# HumidTempSleep_Feather_001sch.net
KiCad netlist of a schematic drawn in EAGLE
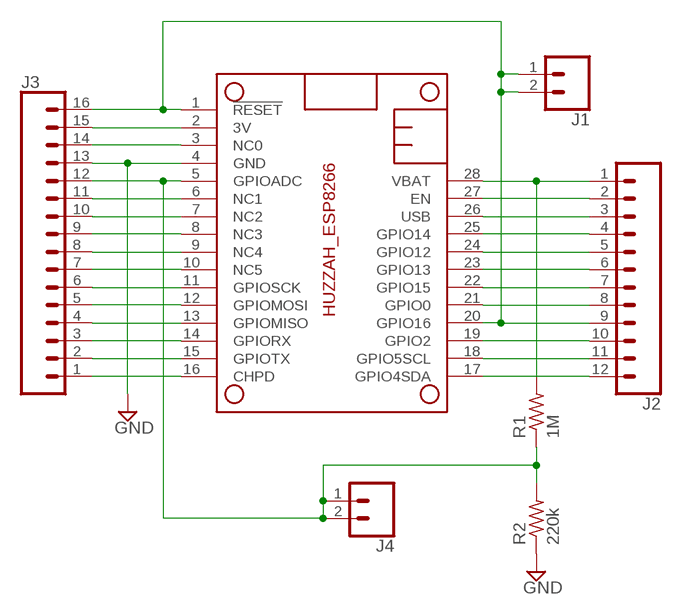
[diagram p0: schematic, sheet 1]

(export (version "E")
  (design (tool "Eeschema 10.0.6"))
  (components
    (comp (ref "J1")
      (value "CONN_02")
      (footprint "eagle-import:1X02")
      (libsource (lib "eagle-import") (part "CONN_02"))
    )
    (comp (ref "J2")
      (value "CONN_12")
      (footprint "eagle-import:1X12")
      (libsource (lib "eagle-import") (part "CONN_12"))
    )
    (comp (ref "J3")
      (value "CONN_16")
      (footprint "eagle-import:1X16")
      (libsource (lib "eagle-import") (part "CONN_16"))
    )
    (comp (ref "J4")
      (value "CONN_02")
      (footprint "eagle-import:1X02")
      (libsource (lib "eagle-import") (part "CONN_02"))
    )
    (comp (ref "MS2")
      (value "FEATHERWING")
      (footprint "eagle-import:FEATHERWING")
      (libsource (lib "eagle-import") (part "FEATHERWING"))
    )
    (comp (ref "R1")
      (value "1M")
      (footprint "eagle-import:R0805")
      (libsource (lib "eagle-import") (part "R-US_R0805"))
    )
    (comp (ref "R2")
      (value "220k")
      (footprint "eagle-import:R0805")
      (libsource (lib "eagle-import") (part "R-US_R0805"))
    )
  )
  (nets
    (net (code "1") (name "GND") (class "Default")
      (node (ref "J3") (pin "13") (pinfunction "13_13") (pintype "passive"))
      (node (ref "MS2") (pin "4") (pinfunction "GND_4") (pintype "power_in"))
      (node (ref "R2") (pin "1") (pinfunction "1_1") (pintype "passive"))
    )
    (net (code "2") (name "Net-(MS2-3V)") (class "Default")
      (node (ref "J3") (pin "15") (pinfunction "15_15") (pintype "passive"))
      (node (ref "MS2") (pin "2") (pinfunction "3V_2") (pintype "power_in"))
    )
    (net (code "3") (name "Net-(MS2-CHPD)") (class "Default")
      (node (ref "J3") (pin "1") (pinfunction "1_1") (pintype "passive"))
      (node (ref "MS2") (pin "16") (pinfunction "CHPD_16") (pintype "passive"))
    )
    (net (code "4") (name "Net-(MS2-EN)") (class "Default")
      (node (ref "J2") (pin "2") (pinfunction "2_2") (pintype "passive"))
      (node (ref "MS2") (pin "27") (pinfunction "EN_27") (pintype "passive"))
    )
    (net (code "5") (name "Net-(MS2-GPIO0)") (class "Default")
      (node (ref "J2") (pin "8") (pinfunction "8_8") (pintype "passive"))
      (node (ref "MS2") (pin "21") (pinfunction "GPIO0_21") (pintype "bidirectional"))
    )
    (net (code "6") (name "Net-(MS2-GPIO2)") (class "Default")
      (node (ref "J2") (pin "10") (pinfunction "10_10") (pintype "passive"))
      (node (ref "MS2") (pin "19") (pinfunction "GPIO2_19") (pintype "bidirectional"))
    )
    (net (code "7") (name "Net-(MS2-GPIO4SDA)") (class "Default")
      (node (ref "J2") (pin "12") (pinfunction "12_12") (pintype "passive"))
      (node (ref "MS2") (pin "17") (pinfunction "GPIO4SDA_17") (pintype "bidirectional"))
    )
    (net (code "8") (name "Net-(MS2-GPIO5SCL)") (class "Default")
      (node (ref "J2") (pin "11") (pinfunction "11_11") (pintype "passive"))
      (node (ref "MS2") (pin "18") (pinfunction "GPIO5SCL_18") (pintype "bidirectional"))
    )
    (net (code "9") (name "Net-(MS2-GPIO12)") (class "Default")
      (node (ref "J2") (pin "5") (pinfunction "5_5") (pintype "passive"))
      (node (ref "MS2") (pin "24") (pinfunction "GPIO12_24") (pintype "bidirectional"))
    )
    (net (code "10") (name "Net-(MS2-GPIO13)") (class "Default")
      (node (ref "J2") (pin "6") (pinfunction "6_6") (pintype "passive"))
      (node (ref "MS2") (pin "23") (pinfunction "GPIO13_23") (pintype "bidirectional"))
    )
    (net (code "11") (name "Net-(MS2-GPIO14)") (class "Default")
      (node (ref "J2") (pin "4") (pinfunction "4_4") (pintype "passive"))
      (node (ref "MS2") (pin "25") (pinfunction "GPIO14_25") (pintype "bidirectional"))
    )
    (net (code "12") (name "Net-(MS2-GPIO15)") (class "Default")
      (node (ref "J2") (pin "7") (pinfunction "7_7") (pintype "passive"))
      (node (ref "MS2") (pin "22") (pinfunction "GPIO15_22") (pintype "bidirectional"))
    )
    (net (code "13") (name "Net-(MS2-GPIO16)") (class "Default")
      (node (ref "J1") (pin "1") (pinfunction "1_1") (pintype "passive"))
      (node (ref "J1") (pin "2") (pinfunction "2_2") (pintype "passive"))
      (node (ref "J2") (pin "9") (pinfunction "9_9") (pintype "passive"))
      (node (ref "J3") (pin "16") (pinfunction "16_16") (pintype "passive"))
      (node (ref "MS2") (pin "1") (pinfunction "~{RESET}_1") (pintype "input"))
      (node (ref "MS2") (pin "20") (pinfunction "GPIO16_20") (pintype "bidirectional"))
    )
    (net (code "14") (name "Net-(MS2-GPIOADC)") (class "Default")
      (node (ref "J3") (pin "12") (pinfunction "12_12") (pintype "passive"))
      (node (ref "J4") (pin "1") (pinfunction "1_1") (pintype "passive"))
      (node (ref "J4") (pin "2") (pinfunction "2_2") (pintype "passive"))
      (node (ref "MS2") (pin "5") (pinfunction "GPIOADC_5") (pintype "bidirectional"))
      (node (ref "R1") (pin "1") (pinfunction "1_1") (pintype "passive"))
      (node (ref "R2") (pin "2") (pinfunction "2_2") (pintype "passive"))
    )
    (net (code "15") (name "Net-(MS2-GPIOMISO)") (class "Default")
      (node (ref "J3") (pin "4") (pinfunction "4_4") (pintype "passive"))
      (node (ref "MS2") (pin "13") (pinfunction "GPIOMISO_13") (pintype "bidirectional"))
    )
    (net (code "16") (name "Net-(MS2-GPIOMOSI)") (class "Default")
      (node (ref "J3") (pin "5") (pinfunction "5_5") (pintype "passive"))
      (node (ref "MS2") (pin "12") (pinfunction "GPIOMOSI_12") (pintype "bidirectional"))
    )
    (net (code "17") (name "Net-(MS2-GPIORX)") (class "Default")
      (node (ref "J3") (pin "3") (pinfunction "3_3") (pintype "passive"))
      (node (ref "MS2") (pin "14") (pinfunction "GPIORX_14") (pintype "bidirectional"))
    )
    (net (code "18") (name "Net-(MS2-GPIOSCK)") (class "Default")
      (node (ref "J3") (pin "6") (pinfunction "6_6") (pintype "passive"))
      (node (ref "MS2") (pin "11") (pinfunction "GPIOSCK_11") (pintype "bidirectional"))
    )
    (net (code "19") (name "Net-(MS2-GPIOTX)") (class "Default")
      (node (ref "J3") (pin "2") (pinfunction "2_2") (pintype "passive"))
      (node (ref "MS2") (pin "15") (pinfunction "GPIOTX_15") (pintype "bidirectional"))
    )
    (net (code "20") (name "Net-(MS2-NC0)") (class "Default")
      (node (ref "J3") (pin "14") (pinfunction "14_14") (pintype "passive"))
      (node (ref "MS2") (pin "3") (pinfunction "NC0_3") (pintype "passive"))
    )
    (net (code "21") (name "Net-(MS2-NC1)") (class "Default")
      (node (ref "J3") (pin "11") (pinfunction "11_11") (pintype "passive"))
      (node (ref "MS2") (pin "6") (pinfunction "NC1_6") (pintype "bidirectional"))
    )
    (net (code "22") (name "Net-(MS2-NC2)") (class "Default")
      (node (ref "J3") (pin "10") (pinfunction "10_10") (pintype "passive"))
      (node (ref "MS2") (pin "7") (pinfunction "NC2_7") (pintype "bidirectional"))
    )
    (net (code "23") (name "Net-(MS2-NC3)") (class "Default")
      (node (ref "J3") (pin "9") (pinfunction "9_9") (pintype "passive"))
      (node (ref "MS2") (pin "8") (pinfunction "NC3_8") (pintype "bidirectional"))
    )
    (net (code "24") (name "Net-(MS2-NC4)") (class "Default")
      (node (ref "J3") (pin "8") (pinfunction "8_8") (pintype "passive"))
      (node (ref "MS2") (pin "9") (pinfunction "NC4_9") (pintype "bidirectional"))
    )
    (net (code "25") (name "Net-(MS2-NC5)") (class "Default")
      (node (ref "J3") (pin "7") (pinfunction "7_7") (pintype "passive"))
      (node (ref "MS2") (pin "10") (pinfunction "NC5_10") (pintype "bidirectional"))
    )
    (net (code "26") (name "Net-(MS2-USB)") (class "Default")
      (node (ref "J2") (pin "3") (pinfunction "3_3") (pintype "passive"))
      (node (ref "MS2") (pin "26") (pinfunction "USB_26") (pintype "power_in"))
    )
    (net (code "27") (name "Net-(MS2-VBAT)") (class "Default")
      (node (ref "J2") (pin "1") (pinfunction "1_1") (pintype "passive"))
      (node (ref "MS2") (pin "28") (pinfunction "VBAT_28") (pintype "power_in"))
      (node (ref "R1") (pin "2") (pinfunction "2_2") (pintype "passive"))
    )
  )
)
